# MainBoard_V100_PSU_DET.net
KiCad netlist of a schematic drawn in Altium Designer
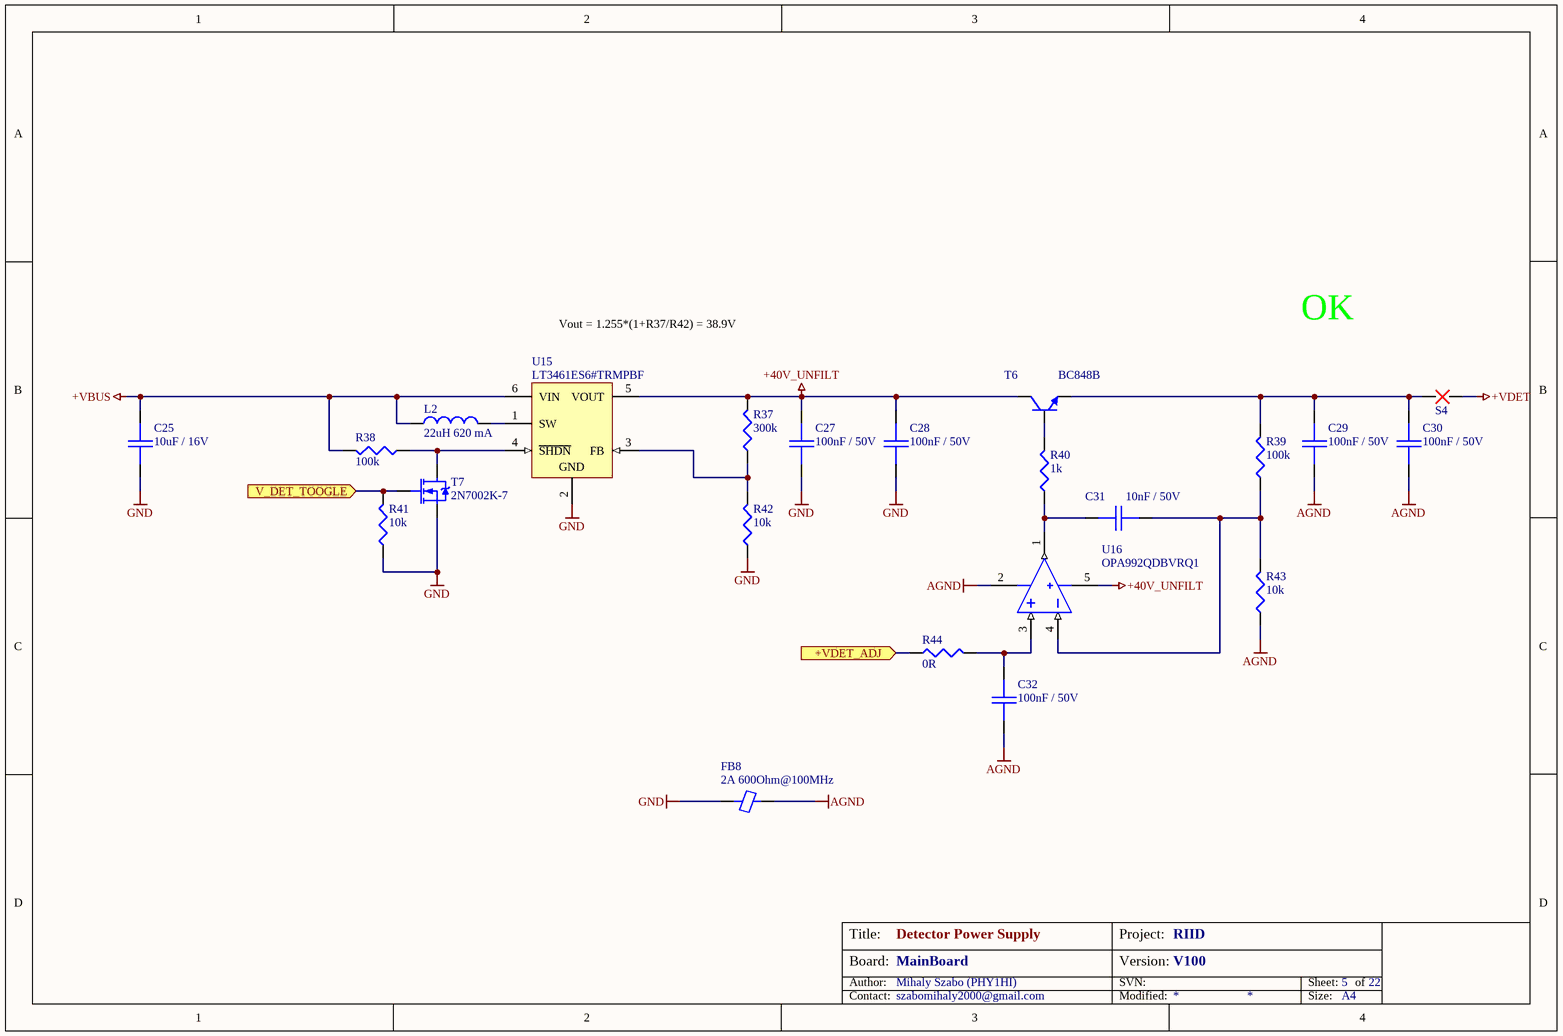
[diagram p0: MainBoard_V100_PSU_DET.SchDoc]

(export (version "E")
  (design (tool "Eeschema 10.0.6"))
  (components
    (comp (ref "C25")
      (value "10uF / 16V")
      (footprint "0805_C")
      (description "10uF 16V X5R")
      (fields (field (name "PART NUMBER") "SMD0805-10uF-16V"))
      (libsource (lib "ALTIUM_DB_LIB") (part "CAP_NONPOL"))
    )
    (comp (ref "C27")
      (value "100nF / 50V")
      (footprint "0805_C")
      (description "100nF 50V X7R")
      (fields (field (name "PART NUMBER") "SMD0805-100nF-50V"))
      (libsource (lib "ALTIUM_DB_LIB") (part "CAP_NONPOL"))
    )
    (comp (ref "C28")
      (value "100nF / 50V")
      (footprint "0805_C")
      (description "100nF 50V X7R")
      (fields (field (name "PART NUMBER") "SMD0805-100nF-50V"))
      (libsource (lib "ALTIUM_DB_LIB") (part "CAP_NONPOL"))
    )
    (comp (ref "C29")
      (value "100nF / 50V")
      (footprint "0805_C")
      (description "100nF 50V X7R")
      (fields (field (name "PART NUMBER") "SMD0805-100nF-50V"))
      (libsource (lib "ALTIUM_DB_LIB") (part "CAP_NONPOL"))
    )
    (comp (ref "C30")
      (value "100nF / 50V")
      (footprint "0805_C")
      (description "100nF 50V X7R")
      (fields (field (name "PART NUMBER") "SMD0805-100nF-50V"))
      (libsource (lib "ALTIUM_DB_LIB") (part "CAP_NONPOL"))
    )
    (comp (ref "C31")
      (value "10nF / 50V")
      (footprint "0805_C")
      (description "10nF 50V X7R")
      (fields (field (name "PART NUMBER") "SMD0805-10nF-50V"))
      (libsource (lib "ALTIUM_DB_LIB") (part "CAP_NONPOL"))
    )
    (comp (ref "C32")
      (value "100nF / 50V")
      (footprint "0805_C")
      (description "100nF 50V X7R")
      (fields (field (name "PART NUMBER") "SMD0805-100nF-50V"))
      (libsource (lib "ALTIUM_DB_LIB") (part "CAP_NONPOL"))
    )
    (comp (ref "FB8")
      (value "2A 600Ohm@100MHz")
      (footprint "0805_FB")
      (description "Ferrite bead 2A 600Ohm@100MHz")
      (fields (field (name "PART NUMBER") "LCBB-601 SMD"))
      (libsource (lib "ALTIUM_DB_LIB") (part "FERRITE_BEAD"))
    )
    (comp (ref "L2")
      (value "22uH 620 mA")
      (footprint "1210")
      (description "22uH 620 mA 1210")
      (fields (field (name "PART NUMBER") "CBC3225T220KR"))
      (libsource (lib "ALTIUM_DB_LIB") (part "INDUCTOR"))
    )
    (comp (ref "R37")
      (value "300k")
      (footprint "0805")
      (description "300k 0805 0.125W 1%")
      (fields (field (name "PART NUMBER") "SMD0805-300k 1%"))
      (libsource (lib "ALTIUM_DB_LIB") (part "RESISTOR"))
    )
    (comp (ref "R38")
      (value "100k")
      (footprint "0805")
      (description "100k 0805 0.125W 5%")
      (fields (field (name "PART NUMBER") "SMD0805-100k 5%"))
      (libsource (lib "ALTIUM_DB_LIB") (part "RESISTOR"))
    )
    (comp (ref "R39")
      (value "100k")
      (footprint "0805")
      (description "100k 0805 0.125W 5%")
      (fields (field (name "PART NUMBER") "SMD0805-100k 5%"))
      (libsource (lib "ALTIUM_DB_LIB") (part "RESISTOR"))
    )
    (comp (ref "R40")
      (value "1k")
      (footprint "0805")
      (description "1k 0805 0.125W 1%")
      (fields (field (name "PART NUMBER") "SMD0805-1k 1%"))
      (libsource (lib "ALTIUM_DB_LIB") (part "RESISTOR"))
    )
    (comp (ref "R41")
      (value "10k")
      (footprint "0805")
      (description "10k 0805 0.125W 1%")
      (fields (field (name "PART NUMBER") "SMD0805-10k 1%"))
      (libsource (lib "ALTIUM_DB_LIB") (part "RESISTOR"))
    )
    (comp (ref "R42")
      (value "10k")
      (footprint "0805")
      (description "10k 0805 0.125W 1%")
      (fields (field (name "PART NUMBER") "SMD0805-10k 1%"))
      (libsource (lib "ALTIUM_DB_LIB") (part "RESISTOR"))
    )
    (comp (ref "R43")
      (value "10k")
      (footprint "0805")
      (description "10k 0805 0.125W 1%")
      (fields (field (name "PART NUMBER") "SMD0805-10k 1%"))
      (libsource (lib "ALTIUM_DB_LIB") (part "RESISTOR"))
    )
    (comp (ref "R44")
      (value "0R")
      (footprint "0805")
      (description "0R 0805 0.125W 5%")
      (fields (field (name "PART NUMBER") "0 R 5%"))
      (libsource (lib "ALTIUM_DB_LIB") (part "RESISTOR"))
    )
    (comp (ref "S4")
      (value "SPLITER")
      (footprint "SPLITER2_30mil_9mil")
      (description "SPLITER2_30mil_9mil")
      (libsource (lib "ALTIUM_DB_LIB") (part "SPLITER"))
    )
    (comp (ref "T6")
      (value "BC848B")
      (footprint "SOT-23")
      (description "Bipolar (BJT) Single Transistor, NPN, 30 V, 100 mA, 300 mW, SOT-23, Surface Mount")
      (libsource (lib "ALTIUM_DB_LIB") (part "BJT_NPN"))
    )
    (comp (ref "T7")
      (value "2N7002K-7")
      (footprint "SOT-23")
      (description "2N7002K-7 Power MOSFET, N Channel, 60 V, 300 mA, 2 ohm, SOT-23, Surface Mount")
      (libsource (lib "ALTIUM_DB_LIB") (part "MOSFET_N_CH"))
    )
    (comp (ref "U15")
      (value "LT3461ES6#TRMPBF")
      (footprint "SOT-23-6L")
      (description "1.3 MHz Step-Up DC/DC Converter with Integrated Schottky, 6-pin SOT23 (S6-6), -40 to 85°C")
      (libsource (lib "ALTIUM_DB_LIB") (part "LT3461"))
    )
    (comp (ref "U16")
      (value "OPA992QDBVRQ1")
      (footprint "SOT-23-5")
      (fields
        (field (name "MOUSER PART NUMBER") "595-INA180A2IDBVR")
        (field (name "MANUFACTURER_PART_NUMBER") "INA180A2IDBVR")
      )
      (libsource (lib "ALTIUM_DB_LIB") (part "OPA992-Q1"))
    )
  )
  (nets
    (net (code "1") (name "+40V_UNFILT") (class "Default")
      (node (ref "C27") (pin "1") (pintype "passive"))
      (node (ref "C28") (pin "1") (pintype "passive"))
      (node (ref "R37") (pin "2") (pintype "passive"))
      (node (ref "T6") (pin "3") (pinfunction "C_3") (pintype "passive"))
      (node (ref "U15") (pin "5") (pinfunction "VOUT_5") (pintype "power_in"))
      (node (ref "U16") (pin "5") (pinfunction "V+_5") (pintype "power_in"))
    )
    (net (code "2") (name "+VBUS") (class "Default")
      (node (ref "C25") (pin "1") (pintype "passive"))
      (node (ref "L2") (pin "1") (pinfunction "1_1") (pintype "passive"))
      (node (ref "R38") (pin "2") (pintype "passive"))
      (node (ref "U15") (pin "6") (pinfunction "VIN_6") (pintype "power_in"))
    )
    (net (code "3") (name "+VDET") (class "Default")
      (node (ref "S4") (pin "2") (pinfunction "2_2") (pintype "passive"))
    )
    (net (code "4") (name "/+VDET_ADJ") (class "Default") (node (ref "R44") (pin "1") (pintype "passive")))
    (net (code "5") (name "/V_DET_TOOGLE") (class "Default")
      (node (ref "R41") (pin "2") (pintype "passive"))
      (node (ref "T7") (pin "1") (pinfunction "G_1") (pintype "passive"))
    )
    (net (code "6") (name "AGND") (class "Default")
      (node (ref "C29") (pin "2") (pintype "passive"))
      (node (ref "C30") (pin "2") (pintype "passive"))
      (node (ref "C32") (pin "1") (pintype "passive"))
      (node (ref "FB8") (pin "2") (pinfunction "2_2") (pintype "passive"))
      (node (ref "R43") (pin "1") (pintype "passive"))
      (node (ref "U16") (pin "2") (pinfunction "V-_2") (pintype "power_in"))
    )
    (net (code "7") (name "GND") (class "Default")
      (node (ref "C25") (pin "2") (pintype "passive"))
      (node (ref "C27") (pin "2") (pintype "passive"))
      (node (ref "C28") (pin "2") (pintype "passive"))
      (node (ref "FB8") (pin "1") (pinfunction "1_1") (pintype "passive"))
      (node (ref "R41") (pin "1") (pintype "passive"))
      (node (ref "R42") (pin "1") (pintype "passive"))
      (node (ref "T7") (pin "2") (pinfunction "S_2") (pintype "passive"))
      (node (ref "U15") (pin "2") (pinfunction "GND_2") (pintype "power_in"))
    )
    (net (code "8") (name "Net-(T6-B)") (class "Default")
      (node (ref "R40") (pin "2") (pintype "passive"))
      (node (ref "T6") (pin "1") (pinfunction "B_1") (pintype "passive"))
    )
    (net (code "9") (name "Net-(T6-E)") (class "Default")
      (node (ref "C29") (pin "1") (pintype "passive"))
      (node (ref "C30") (pin "1") (pintype "passive"))
      (node (ref "R39") (pin "2") (pintype "passive"))
      (node (ref "S4") (pin "1") (pinfunction "1_1") (pintype "passive"))
      (node (ref "T6") (pin "2") (pinfunction "E_2") (pintype "passive"))
    )
    (net (code "10") (name "Net-(T7-D)") (class "Default")
      (node (ref "R38") (pin "1") (pintype "passive"))
      (node (ref "T7") (pin "3") (pinfunction "D_3") (pintype "passive"))
      (node (ref "U15") (pin "4") (pinfunction "~{SHDN}_4") (pintype "input"))
    )
    (net (code "11") (name "Net-(U15-FB)") (class "Default")
      (node (ref "R37") (pin "1") (pintype "passive"))
      (node (ref "R42") (pin "2") (pintype "passive"))
      (node (ref "U15") (pin "3") (pinfunction "FB_3") (pintype "input"))
    )
    (net (code "12") (name "Net-(U15-SW)") (class "Default")
      (node (ref "L2") (pin "2") (pinfunction "2_2") (pintype "passive"))
      (node (ref "U15") (pin "1") (pinfunction "SW_1") (pintype "passive"))
    )
    (net (code "13") (name "Net-(U16-IN+)") (class "Default")
      (node (ref "C32") (pin "2") (pintype "passive"))
      (node (ref "R44") (pin "2") (pintype "passive"))
      (node (ref "U16") (pin "3") (pinfunction "IN+_3") (pintype "input"))
    )
    (net (code "14") (name "Net-(U16-IN-)") (class "Default")
      (node (ref "C31") (pin "2") (pintype "passive"))
      (node (ref "R39") (pin "1") (pintype "passive"))
      (node (ref "R43") (pin "2") (pintype "passive"))
      (node (ref "U16") (pin "4") (pinfunction "IN-_4") (pintype "input"))
    )
    (net (code "15") (name "Net-(U16-OUT)") (class "Default")
      (node (ref "C31") (pin "1") (pintype "passive"))
      (node (ref "R40") (pin "1") (pintype "passive"))
      (node (ref "U16") (pin "1") (pinfunction "OUT_1") (pintype "output"))
    )
  )
)
